# Current_detector.net
KiCad netlist of a schematic drawn in Altium Designer
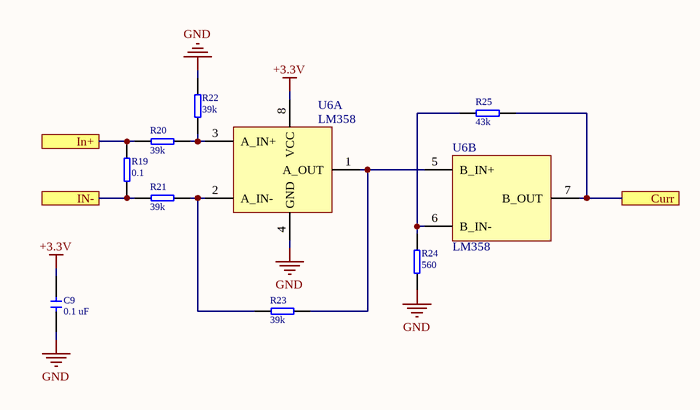
[diagram p0: Current_detector.SchDoc]

(export (version "E")
  (design (tool "Eeschema 10.0.6"))
  (components
    (comp (ref "C9")
      (value "0.1 uF")
      (footprint "CERCAP 0402")
      (description "Capacitor")
      (fields (field (name "Comment") "CERCAP 0402 0.1 uF * X7R"))
      (libsource (lib "!main") (part "!Capacitor"))
    )
    (comp (ref "R19")
      (value "0.1")
      (footprint "RES 1206")
      (description "Resistor")
      (fields (field (name "Comment") "RES 1206 0.1"))
      (libsource (lib "!main") (part "!Resistor"))
    )
    (comp (ref "R20")
      (value "39k")
      (footprint "RES 0402")
      (description "Resistor")
      (fields (field (name "Comment") "RES 0402 39k"))
      (libsource (lib "!main") (part "!Resistor"))
    )
    (comp (ref "R21")
      (value "39k")
      (footprint "RES 0402")
      (description "Resistor")
      (fields (field (name "Comment") "RES 0402 39k"))
      (libsource (lib "!main") (part "!Resistor"))
    )
    (comp (ref "R22")
      (value "39k")
      (footprint "RES 0402")
      (description "Resistor")
      (fields (field (name "Comment") "RES 0402 39k"))
      (libsource (lib "!main") (part "!Resistor"))
    )
    (comp (ref "R23")
      (value "39k")
      (footprint "RES 0402")
      (description "Resistor")
      (fields (field (name "Comment") "RES 0402 39k"))
      (libsource (lib "!main") (part "!Resistor"))
    )
    (comp (ref "R24")
      (value "560")
      (footprint "RES 0402")
      (description "Resistor")
      (fields (field (name "Comment") "RES 0402 560"))
      (libsource (lib "!main") (part "!Resistor"))
    )
    (comp (ref "R25")
      (value "43k")
      (footprint "RES 0402")
      (description "Resistor")
      (fields (field (name "Comment") "RES 0402 43k"))
      (libsource (lib "!main") (part "!Resistor"))
    )
    (comp (ref "U6")
      (value "LM358")
      (footprint "SO-8")
      (description "Operational amplifier")
      (libsource (lib "analog") (part "DualOpAmp"))
    )
  )
  (nets
    (net (code "1") (name "+3.3V") (class "Default")
      (node (ref "C9") (pin "2") (pintype "passive"))
      (node (ref "U6") (pin "8") (pinfunction "VCC_8") (pintype "passive"))
    )
    (net (code "2") (name "/Curr") (class "Default")
      (node (ref "R25") (pin "2") (pinfunction "12_2") (pintype "passive"))
      (node (ref "U6") (pin "7") (pinfunction "B_OUT_7") (pintype "passive"))
    )
    (net (code "3") (name "/IN-") (class "Default")
      (node (ref "R19") (pin "1") (pinfunction "11_1") (pintype "passive"))
      (node (ref "R21") (pin "1") (pinfunction "11_1") (pintype "passive"))
    )
    (net (code "4") (name "/In+") (class "Default")
      (node (ref "R19") (pin "2") (pinfunction "12_2") (pintype "passive"))
      (node (ref "R20") (pin "1") (pinfunction "11_1") (pintype "passive"))
    )
    (net (code "5") (name "GND") (class "Default")
      (node (ref "C9") (pin "1") (pintype "passive"))
      (node (ref "R22") (pin "2") (pinfunction "12_2") (pintype "passive"))
      (node (ref "R24") (pin "1") (pinfunction "11_1") (pintype "passive"))
      (node (ref "U6") (pin "4") (pinfunction "GND_4") (pintype "passive"))
    )
    (net (code "6") (name "Net-(R20-12)") (class "Default")
      (node (ref "R20") (pin "2") (pinfunction "12_2") (pintype "passive"))
      (node (ref "R22") (pin "1") (pinfunction "11_1") (pintype "passive"))
      (node (ref "U6") (pin "3") (pinfunction "A_IN+_3") (pintype "passive"))
    )
    (net (code "7") (name "Net-(R21-12)") (class "Default")
      (node (ref "R21") (pin "2") (pinfunction "12_2") (pintype "passive"))
      (node (ref "R23") (pin "1") (pinfunction "11_1") (pintype "passive"))
      (node (ref "U6") (pin "2") (pinfunction "A_IN-_2") (pintype "passive"))
    )
    (net (code "8") (name "Net-(R23-12)") (class "Default")
      (node (ref "R23") (pin "2") (pinfunction "12_2") (pintype "passive"))
      (node (ref "U6") (pin "1") (pinfunction "A_OUT_1") (pintype "passive"))
      (node (ref "U6") (pin "5") (pinfunction "B_IN+_5") (pintype "passive"))
    )
    (net (code "9") (name "Net-(R24-12)") (class "Default")
      (node (ref "R24") (pin "2") (pinfunction "12_2") (pintype "passive"))
      (node (ref "R25") (pin "1") (pinfunction "11_1") (pintype "passive"))
      (node (ref "U6") (pin "6") (pinfunction "B_IN-_6") (pintype "passive"))
    )
  )
)
